# Logic.net
KiCad netlist of a schematic drawn in Altium Designer
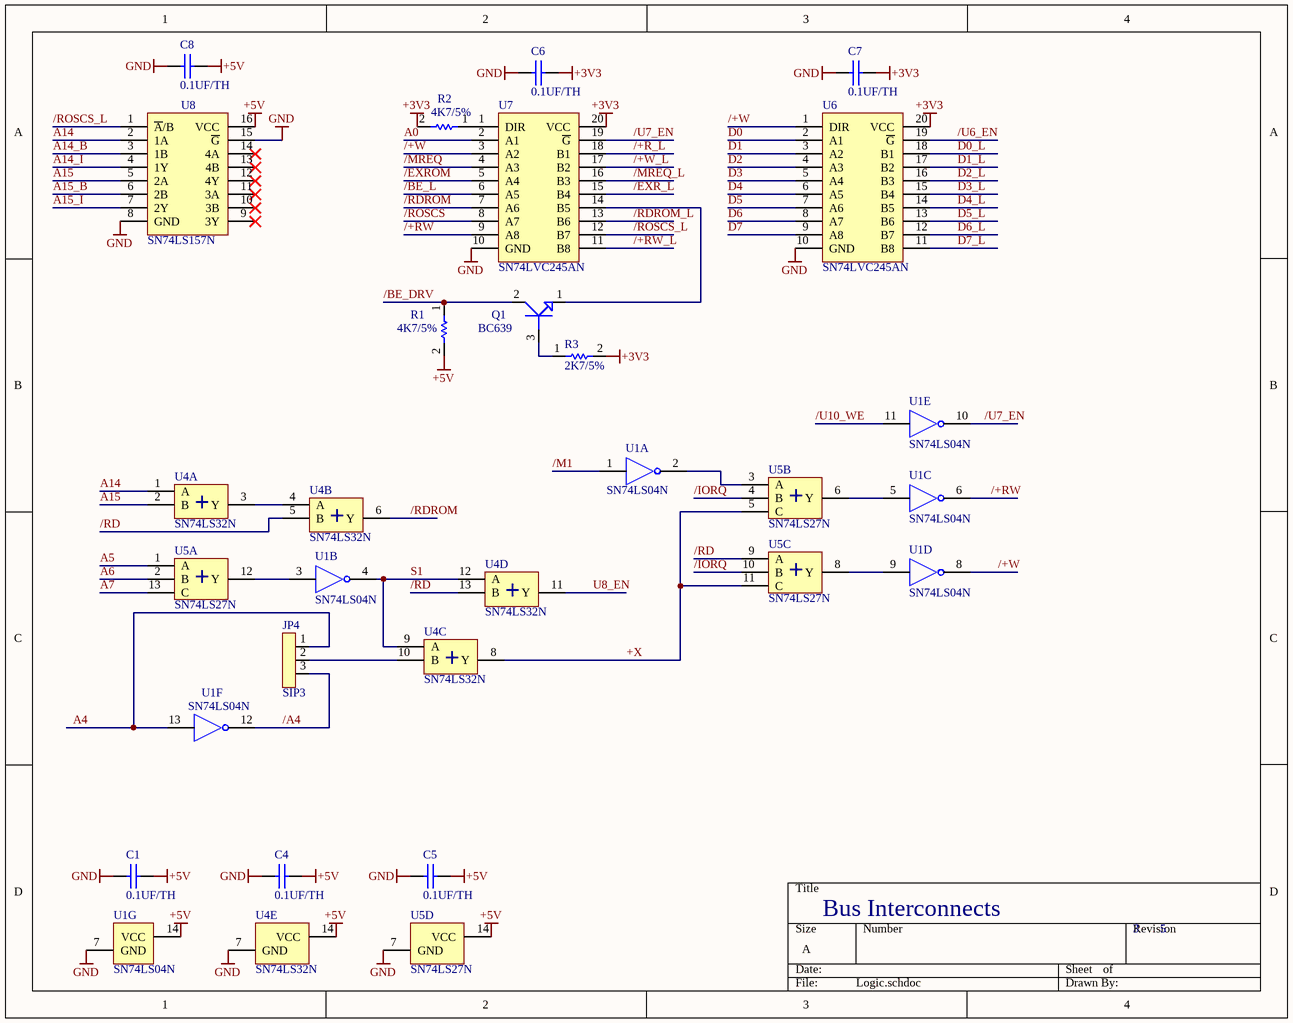
[diagram p0: Logic.schdoc]

(export (version "E")
  (design (tool "Eeschema 10.0.6"))
  (components
    (comp (ref "C1")
      (value "0.1UF/TH")
      (footprint "CAPH5")
      (description "0.1 µF ±10% 50V Ceramic Capacitor X7R Radial")
      (fields (field (name "MFG") "Vishay"))
      (libsource (lib "CapacitorsTH") (part "0.1UF/TH"))
    )
    (comp (ref "C4")
      (value "0.1UF/TH")
      (footprint "CAPH5")
      (description "0.1 µF ±10% 50V Ceramic Capacitor X7R Radial")
      (fields (field (name "MFG") "Vishay"))
      (libsource (lib "CapacitorsTH") (part "0.1UF/TH"))
    )
    (comp (ref "C5")
      (value "0.1UF/TH")
      (footprint "CAPH5")
      (description "0.1 µF ±10% 50V Ceramic Capacitor X7R Radial")
      (fields (field (name "MFG") "Vishay"))
      (libsource (lib "CapacitorsTH") (part "0.1UF/TH"))
    )
    (comp (ref "C6")
      (value "0.1UF/TH")
      (footprint "CAPH5")
      (description "0.1 µF ±10% 50V Ceramic Capacitor X7R Radial")
      (fields (field (name "MFG") "Vishay"))
      (libsource (lib "CapacitorsTH") (part "0.1UF/TH"))
    )
    (comp (ref "C7")
      (value "0.1UF/TH")
      (footprint "CAPH5")
      (description "0.1 µF ±10% 50V Ceramic Capacitor X7R Radial")
      (fields (field (name "MFG") "Vishay"))
      (libsource (lib "CapacitorsTH") (part "0.1UF/TH"))
    )
    (comp (ref "C8")
      (value "0.1UF/TH")
      (footprint "CAPH5")
      (description "0.1 µF ±10% 50V Ceramic Capacitor X7R Radial")
      (fields (field (name "MFG") "Vishay"))
      (libsource (lib "CapacitorsTH") (part "0.1UF/TH"))
    )
    (comp (ref "JP4") (value "SIP3") (footprint "SIP3") (libsource (lib "Connectors") (part "SIP3")))
    (comp (ref "Q1")
      (value "BC639")
      (footprint "TO92")
      (description "Bipolar (BJT) Transistor NPN 80 V 1 A 200MHz 625 mW Through Hole TO-92 (TO-226)")
      (fields (field (name "MFG") "Infineon"))
      (libsource (lib "MiscSemi") (part "BC639"))
    )
    (comp (ref "R1")
      (value "4K7/5%")
      (footprint "CF18")
      (description "RES 4.7K OHM 5% 1/8W AXIAL")
      (fields (field (name "MFG") "Stackpole"))
      (libsource (lib "ResistorsTH") (part "4K7/5%"))
    )
    (comp (ref "R2")
      (value "4K7/5%")
      (footprint "CF18")
      (description "RES 4.7K OHM 5% 1/8W AXIAL")
      (fields (field (name "MFG") "Stackpole"))
      (libsource (lib "ResistorsTH") (part "4K7/5%"))
    )
    (comp (ref "R3")
      (value "2K7/5%")
      (footprint "CF18")
      (description "RES 2.7K OHM 5% 1/8W AXIAL")
      (fields (field (name "MFG") "Stackpole"))
      (libsource (lib "ResistorsTH") (part "2K7/5%"))
    )
    (comp (ref "U1")
      (value "SN74LS04N")
      (footprint "dip14")
      (description "Inverter IC 6 Channel 14-PDIP")
      (fields (field (name "MFG") "TI"))
      (libsource (lib "DigitalTH") (part "SN74LS04N"))
    )
    (comp (ref "U4")
      (value "SN74LS32N")
      (footprint "dip14")
      (description "IC GATE OR 4CH 2-INP 14DIP")
      (fields (field (name "MFG") "TI"))
      (libsource (lib "DigitalTH") (part "SN74LS32N"))
    )
    (comp (ref "U5")
      (value "SN74LS27N")
      (footprint "dip14")
      (description "NOR Gate IC 3 Channel 14-PDIP")
      (fields (field (name "MFG") "TI"))
      (libsource (lib "DigitalTH") (part "SN74LS27N"))
    )
    (comp (ref "U6")
      (value "SN74LVC245AN")
      (footprint "DIP20")
      (description "Transceiver, Non-Inverting 1 Element 8 Bit per Element 3-State Output 20-PDIP")
      (fields (field (name "MFG") "TI"))
      (libsource (lib "DigitalTH") (part "SN74LVC245AN"))
    )
    (comp (ref "U7")
      (value "SN74LVC245AN")
      (footprint "DIP20")
      (description "Transceiver, Non-Inverting 1 Element 8 Bit per Element 3-State Output 20-PDIP")
      (fields (field (name "MFG") "TI"))
      (libsource (lib "DigitalTH") (part "SN74LVC245AN"))
    )
    (comp (ref "U8")
      (value "SN74LS157N")
      (footprint "DIP16")
      (description "IC MULTIPLEXER 4 X 2:1 16DIP")
      (fields (field (name "MFG") "TI"))
      (libsource (lib "DigitalTH") (part "SN74LS157N"))
    )
  )
  (nets
    (net (code "1") (name "+3V3") (class "Default")
      (node (ref "C6") (pin "2") (pintype "passive"))
      (node (ref "C7") (pin "2") (pintype "passive"))
      (node (ref "R2") (pin "2") (pinfunction "2_2") (pintype "passive"))
      (node (ref "R3") (pin "2") (pinfunction "2_2") (pintype "passive"))
      (node (ref "U6") (pin "20") (pinfunction "VCC_20") (pintype "passive"))
      (node (ref "U7") (pin "20") (pinfunction "VCC_20") (pintype "passive"))
    )
    (net (code "2") (name "+5V") (class "Default")
      (node (ref "C1") (pin "2") (pintype "passive"))
      (node (ref "C4") (pin "2") (pintype "passive"))
      (node (ref "C5") (pin "2") (pintype "passive"))
      (node (ref "C8") (pin "2") (pintype "passive"))
      (node (ref "R1") (pin "2") (pinfunction "2_2") (pintype "passive"))
      (node (ref "U1") (pin "14") (pinfunction "VCC_14") (pintype "passive"))
      (node (ref "U4") (pin "14") (pinfunction "VCC_14") (pintype "passive"))
      (node (ref "U5") (pin "14") (pinfunction "VCC_14") (pintype "passive"))
      (node (ref "U8") (pin "16") (pinfunction "VCC_16") (pintype "passive"))
    )
    (net (code "3") (name "/+X") (class "Default")
      (node (ref "U4") (pin "8") (pinfunction "Y_8") (pintype "passive"))
      (node (ref "U5") (pin "11") (pinfunction "C_11") (pintype "passive"))
      (node (ref "U5") (pin "5") (pinfunction "C_5") (pintype "passive"))
    )
    (net (code "4") (name "/A0") (class "Default")
      (node (ref "U7") (pin "2") (pinfunction "A1_2") (pintype "passive"))
    )
    (net (code "5") (name "/A4") (class "Default")
      (node (ref "JP4") (pin "1") (pintype "passive"))
      (node (ref "U1") (pin "13") (pintype "passive"))
    )
    (net (code "6") (name "/A5") (class "Default")
      (node (ref "U5") (pin "1") (pinfunction "A_1") (pintype "passive"))
    )
    (net (code "7") (name "/A6") (class "Default")
      (node (ref "U5") (pin "2") (pinfunction "B_2") (pintype "passive"))
    )
    (net (code "8") (name "/A7") (class "Default")
      (node (ref "U5") (pin "13") (pinfunction "C_13") (pintype "passive"))
    )
    (net (code "9") (name "/A14") (class "Default")
      (node (ref "U4") (pin "1") (pinfunction "A_1") (pintype "passive"))
      (node (ref "U8") (pin "2") (pinfunction "1A_2") (pintype "passive"))
    )
    (net (code "10") (name "/A14_B") (class "Default")
      (node (ref "U8") (pin "3") (pinfunction "1B_3") (pintype "passive"))
    )
    (net (code "11") (name "/A14_I") (class "Default")
      (node (ref "U8") (pin "4") (pinfunction "1Y_4") (pintype "passive"))
    )
    (net (code "12") (name "/A15") (class "Default")
      (node (ref "U4") (pin "2") (pinfunction "B_2") (pintype "passive"))
      (node (ref "U8") (pin "5") (pinfunction "2A_5") (pintype "passive"))
    )
    (net (code "13") (name "/A15_B") (class "Default")
      (node (ref "U8") (pin "6") (pinfunction "2B_6") (pintype "passive"))
    )
    (net (code "14") (name "/A15_I") (class "Default")
      (node (ref "U8") (pin "7") (pinfunction "2Y_7") (pintype "passive"))
    )
    (net (code "15") (name "/D0") (class "Default")
      (node (ref "U6") (pin "2") (pinfunction "A1_2") (pintype "passive"))
    )
    (net (code "16") (name "/D0_L") (class "Default")
      (node (ref "U6") (pin "18") (pinfunction "B1_18") (pintype "passive"))
    )
    (net (code "17") (name "/D1") (class "Default")
      (node (ref "U6") (pin "3") (pinfunction "A2_3") (pintype "passive"))
    )
    (net (code "18") (name "/D1_L") (class "Default")
      (node (ref "U6") (pin "17") (pinfunction "B2_17") (pintype "passive"))
    )
    (net (code "19") (name "/D2") (class "Default")
      (node (ref "U6") (pin "4") (pinfunction "A3_4") (pintype "passive"))
    )
    (net (code "20") (name "/D2_L") (class "Default")
      (node (ref "U6") (pin "16") (pinfunction "B3_16") (pintype "passive"))
    )
    (net (code "21") (name "/D3") (class "Default")
      (node (ref "U6") (pin "5") (pinfunction "A4_5") (pintype "passive"))
    )
    (net (code "22") (name "/D3_L") (class "Default")
      (node (ref "U6") (pin "15") (pinfunction "B4_15") (pintype "passive"))
    )
    (net (code "23") (name "/D4") (class "Default")
      (node (ref "U6") (pin "6") (pinfunction "A5_6") (pintype "passive"))
    )
    (net (code "24") (name "/D4_L") (class "Default")
      (node (ref "U6") (pin "14") (pinfunction "B5_14") (pintype "passive"))
    )
    (net (code "25") (name "/D5") (class "Default")
      (node (ref "U6") (pin "7") (pinfunction "A6_7") (pintype "passive"))
    )
    (net (code "26") (name "/D5_L") (class "Default")
      (node (ref "U6") (pin "13") (pinfunction "B6_13") (pintype "passive"))
    )
    (net (code "27") (name "/D6") (class "Default")
      (node (ref "U6") (pin "8") (pinfunction "A7_8") (pintype "passive"))
    )
    (net (code "28") (name "/D6_L") (class "Default")
      (node (ref "U6") (pin "12") (pinfunction "B7_12") (pintype "passive"))
    )
    (net (code "29") (name "/D7") (class "Default")
      (node (ref "U6") (pin "9") (pinfunction "A8_9") (pintype "passive"))
    )
    (net (code "30") (name "/D7_L") (class "Default")
      (node (ref "U6") (pin "11") (pinfunction "B8_11") (pintype "passive"))
    )
    (net (code "31") (name "/S1") (class "Default")
      (node (ref "U1") (pin "4") (pintype "passive"))
      (node (ref "U4") (pin "12") (pinfunction "A_12") (pintype "passive"))
      (node (ref "U4") (pin "9") (pinfunction "A_9") (pintype "passive"))
    )
    (net (code "32") (name "/U8_EN") (class "Default")
      (node (ref "U4") (pin "11") (pinfunction "Y_11") (pintype "passive"))
    )
    (net (code "33") (name "/{slash}+RW") (class "Default")
      (node (ref "U1") (pin "6") (pintype "passive"))
      (node (ref "U7") (pin "9") (pinfunction "A8_9") (pintype "passive"))
    )
    (net (code "34") (name "/{slash}+RW_L") (class "Default")
      (node (ref "U7") (pin "11") (pinfunction "B8_11") (pintype "passive"))
    )
    (net (code "35") (name "/{slash}+R_L") (class "Default")
      (node (ref "U7") (pin "18") (pinfunction "B1_18") (pintype "passive"))
    )
    (net (code "36") (name "/{slash}+W") (class "Default")
      (node (ref "U1") (pin "8") (pintype "passive"))
      (node (ref "U6") (pin "1") (pinfunction "DIR_1") (pintype "passive"))
      (node (ref "U7") (pin "3") (pinfunction "A2_3") (pintype "passive"))
    )
    (net (code "37") (name "/{slash}+W_L") (class "Default")
      (node (ref "U7") (pin "17") (pinfunction "B2_17") (pintype "passive"))
    )
    (net (code "38") (name "/{slash}A4") (class "Default")
      (node (ref "JP4") (pin "3") (pintype "passive"))
      (node (ref "U1") (pin "12") (pintype "passive"))
    )
    (net (code "39") (name "/{slash}BE_DRV") (class "Default")
      (node (ref "Q1") (pin "2") (pinfunction "COLLECTOR_2") (pintype "passive"))
      (node (ref "R1") (pin "1") (pinfunction "1_1") (pintype "passive"))
    )
    (net (code "40") (name "/{slash}BE_L") (class "Default")
      (node (ref "U7") (pin "6") (pinfunction "A5_6") (pintype "passive"))
    )
    (net (code "41") (name "/{slash}EXROM") (class "Default")
      (node (ref "U7") (pin "5") (pinfunction "A4_5") (pintype "passive"))
    )
    (net (code "42") (name "/{slash}EXR_L") (class "Default")
      (node (ref "U7") (pin "15") (pinfunction "B4_15") (pintype "passive"))
    )
    (net (code "43") (name "/{slash}IORQ") (class "Default")
      (node (ref "U5") (pin "10") (pinfunction "B_10") (pintype "passive"))
      (node (ref "U5") (pin "4") (pinfunction "B_4") (pintype "passive"))
    )
    (net (code "44") (name "/{slash}M1") (class "Default") (node (ref "U1") (pin "1") (pintype "passive")))
    (net (code "45") (name "/{slash}MREQ") (class "Default")
      (node (ref "U7") (pin "4") (pinfunction "A3_4") (pintype "passive"))
    )
    (net (code "46") (name "/{slash}MREQ_L") (class "Default")
      (node (ref "U7") (pin "16") (pinfunction "B3_16") (pintype "passive"))
    )
    (net (code "47") (name "/{slash}RD") (class "Default")
      (node (ref "U4") (pin "13") (pinfunction "B_13") (pintype "passive"))
      (node (ref "U4") (pin "5") (pinfunction "B_5") (pintype "passive"))
      (node (ref "U5") (pin "9") (pinfunction "A_9") (pintype "passive"))
    )
    (net (code "48") (name "/{slash}RDROM") (class "Default")
      (node (ref "U4") (pin "6") (pinfunction "Y_6") (pintype "passive"))
      (node (ref "U7") (pin "7") (pinfunction "A6_7") (pintype "passive"))
    )
    (net (code "49") (name "/{slash}RDROM_L") (class "Default")
      (node (ref "U7") (pin "13") (pinfunction "B6_13") (pintype "passive"))
    )
    (net (code "50") (name "/{slash}ROSCS") (class "Default")
      (node (ref "U7") (pin "8") (pinfunction "A7_8") (pintype "passive"))
    )
    (net (code "51") (name "/{slash}ROSCS_L") (class "Default")
      (node (ref "U7") (pin "12") (pinfunction "B7_12") (pintype "passive"))
      (node (ref "U8") (pin "1") (pinfunction "~{A}/B_1") (pintype "passive"))
    )
    (net (code "52") (name "/{slash}U6_EN") (class "Default")
      (node (ref "U6") (pin "19") (pinfunction "~{G}_19") (pintype "passive"))
    )
    (net (code "53") (name "/{slash}U7_EN") (class "Default")
      (node (ref "U1") (pin "10") (pintype "passive"))
      (node (ref "U7") (pin "19") (pinfunction "~{G}_19") (pintype "passive"))
    )
    (net (code "54") (name "/{slash}U10_WE") (class "Default")
      (node (ref "U1") (pin "11") (pintype "passive"))
    )
    (net (code "55") (name "GND") (class "Default")
      (node (ref "C1") (pin "1") (pintype "passive"))
      (node (ref "C4") (pin "1") (pintype "passive"))
      (node (ref "C5") (pin "1") (pintype "passive"))
      (node (ref "C6") (pin "1") (pintype "passive"))
      (node (ref "C7") (pin "1") (pintype "passive"))
      (node (ref "C8") (pin "1") (pintype "passive"))
      (node (ref "U1") (pin "7") (pinfunction "GND_7") (pintype "passive"))
      (node (ref "U4") (pin "7") (pinfunction "GND_7") (pintype "passive"))
      (node (ref "U5") (pin "7") (pinfunction "GND_7") (pintype "passive"))
      (node (ref "U6") (pin "10") (pinfunction "GND_10") (pintype "passive"))
      (node (ref "U7") (pin "10") (pinfunction "GND_10") (pintype "passive"))
      (node (ref "U8") (pin "15") (pinfunction "~{G}_15") (pintype "passive"))
      (node (ref "U8") (pin "8") (pinfunction "GND_8") (pintype "passive"))
    )
    (net (code "56") (name "Net-(Q1-BASE)") (class "Default")
      (node (ref "Q1") (pin "3") (pinfunction "BASE_3") (pintype "passive"))
      (node (ref "R3") (pin "1") (pinfunction "1_1") (pintype "passive"))
    )
    (net (code "57") (name "Net-(Q1-EMITTER)") (class "Default")
      (node (ref "Q1") (pin "1") (pinfunction "EMITTER_1") (pintype "passive"))
      (node (ref "U7") (pin "14") (pinfunction "B5_14") (pintype "passive"))
    )
    (net (code "58") (name "Net-(U4A-Y)") (class "Default")
      (node (ref "U4") (pin "3") (pinfunction "Y_3") (pintype "passive"))
      (node (ref "U4") (pin "4") (pinfunction "A_4") (pintype "passive"))
    )
    (net (code "59") (name "Net-(U4C-B)") (class "Default")
      (node (ref "JP4") (pin "2") (pintype "passive"))
      (node (ref "U4") (pin "10") (pinfunction "B_10") (pintype "passive"))
    )
    (net (code "60") (name "Net-(U5A-Y)") (class "Default")
      (node (ref "U1") (pin "3") (pintype "passive"))
      (node (ref "U5") (pin "12") (pinfunction "Y_12") (pintype "passive"))
    )
    (net (code "61") (name "Net-(U5B-A)") (class "Default")
      (node (ref "U1") (pin "2") (pintype "passive"))
      (node (ref "U5") (pin "3") (pinfunction "A_3") (pintype "passive"))
    )
    (net (code "62") (name "Net-(U5B-Y)") (class "Default")
      (node (ref "U1") (pin "5") (pintype "passive"))
      (node (ref "U5") (pin "6") (pinfunction "Y_6") (pintype "passive"))
    )
    (net (code "63") (name "Net-(U5C-Y)") (class "Default")
      (node (ref "U1") (pin "9") (pintype "passive"))
      (node (ref "U5") (pin "8") (pinfunction "Y_8") (pintype "passive"))
    )
    (net (code "64") (name "Net-(U7-DIR)") (class "Default")
      (node (ref "R2") (pin "1") (pinfunction "1_1") (pintype "passive"))
      (node (ref "U7") (pin "1") (pinfunction "DIR_1") (pintype "passive"))
    )
    (net (code "65") (name "unconnected-(U8-3A-Pad11)") (class "Default")
      (node (ref "U8") (pin "11") (pinfunction "3A_11") (pintype "passive+no_connect"))
    )
    (net (code "66") (name "unconnected-(U8-3B-Pad10)") (class "Default")
      (node (ref "U8") (pin "10") (pinfunction "3B_10") (pintype "passive+no_connect"))
    )
    (net (code "67") (name "unconnected-(U8-3Y-Pad9)") (class "Default")
      (node (ref "U8") (pin "9") (pinfunction "3Y_9") (pintype "passive+no_connect"))
    )
    (net (code "68") (name "unconnected-(U8-4A-Pad14)") (class "Default")
      (node (ref "U8") (pin "14") (pinfunction "4A_14") (pintype "passive+no_connect"))
    )
    (net (code "69") (name "unconnected-(U8-4B-Pad13)") (class "Default")
      (node (ref "U8") (pin "13") (pinfunction "4B_13") (pintype "passive+no_connect"))
    )
    (net (code "70") (name "unconnected-(U8-4Y-Pad12)") (class "Default")
      (node (ref "U8") (pin "12") (pinfunction "4Y_12") (pintype "passive+no_connect"))
    )
  )
)
